# arduino.net
KiCad netlist of a schematic drawn in EAGLE
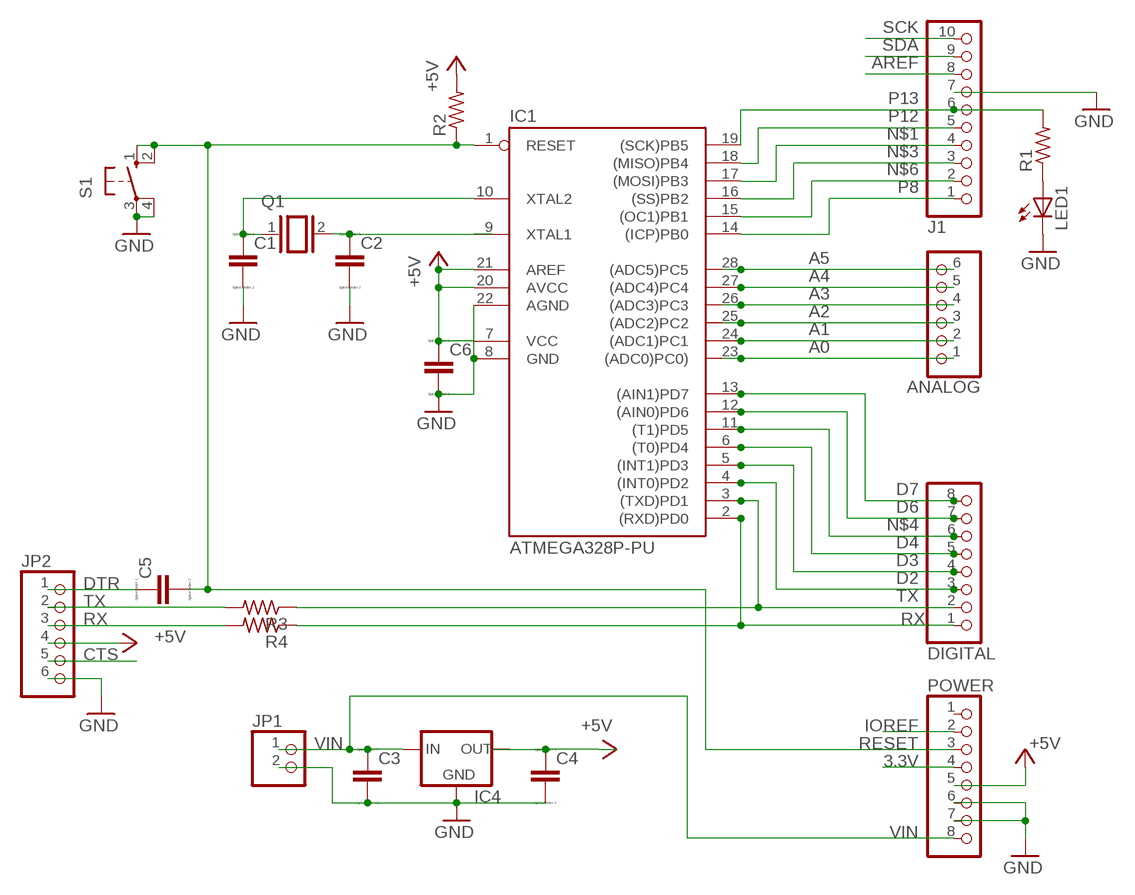
[diagram p0: schematic, sheet 1]

(export (version "E")
  (design (tool "Eeschema 10.0.6"))
  (components
    (comp (ref "ANALOG")
      (value "PINHD-1X6")
      (footprint "eagle-import:1X06")
      (libsource (lib "eagle-import") (part "PINHD-1X6"))
    )
    (comp (ref "C1")
      (value "C-EU050-025X075")
      (footprint "eagle-import:C050-025X075")
      (libsource (lib "eagle-import") (part "C-EU050-025X075"))
    )
    (comp (ref "C2")
      (value "C-EU050-025X075")
      (footprint "eagle-import:C050-025X075")
      (libsource (lib "eagle-import") (part "C-EU050-025X075"))
    )
    (comp (ref "C3")
      (value "C-EU050-025X075")
      (footprint "eagle-import:C050-025X075")
      (libsource (lib "eagle-import") (part "C-EU050-025X075"))
    )
    (comp (ref "C4")
      (value "C-EU050-025X075")
      (footprint "eagle-import:C050-025X075")
      (libsource (lib "eagle-import") (part "C-EU050-025X075"))
    )
    (comp (ref "C5")
      (value "C-EU050-025X075")
      (footprint "eagle-import:C050-025X075")
      (libsource (lib "eagle-import") (part "C-EU050-025X075"))
    )
    (comp (ref "C6")
      (value "C-EU050-025X075")
      (footprint "eagle-import:C050-025X075")
      (libsource (lib "eagle-import") (part "C-EU050-025X075"))
    )
    (comp (ref "DIGITAL")
      (value "PINHD-1X8TH")
      (footprint "eagle-import:1X08-TH")
      (libsource (lib "eagle-import") (part "PINHD-1X8TH"))
    )
    (comp (ref "IC1")
      (value "ATMEGA328P-PU")
      (footprint "eagle-import:DIL28-3")
      (libsource (lib "eagle-import") (part "ATMEGA328P-PU"))
    )
    (comp (ref "IC4")
      (value "78XXS")
      (footprint "eagle-import:78XXS")
      (libsource (lib "eagle-import") (part "78XXS"))
    )
    (comp (ref "J1")
      (value "PINHD-1X10TH")
      (footprint "eagle-import:1X10-TH")
      (libsource (lib "eagle-import") (part "PINHD-1X10TH"))
    )
    (comp (ref "JP1")
      (value "PINHD-1X2")
      (footprint "eagle-import:1X02")
      (libsource (lib "eagle-import") (part "PINHD-1X2"))
    )
    (comp (ref "JP2")
      (value "PINHD-1X6")
      (footprint "eagle-import:1X06")
      (libsource (lib "eagle-import") (part "PINHD-1X6"))
    )
    (comp (ref "LED1")
      (value "LED3MM")
      (footprint "eagle-import:LED3MM")
      (libsource (lib "eagle-import") (part "LED3MM"))
    )
    (comp (ref "POWER")
      (value "PINHD-1X8TH")
      (footprint "eagle-import:1X08-TH")
      (libsource (lib "eagle-import") (part "PINHD-1X8TH"))
    )
    (comp (ref "Q1")
      (value "XTAL/S")
      (footprint "eagle-import:QS")
      (libsource (lib "eagle-import") (part "XTAL/S"))
    )
    (comp (ref "R1")
      (value "R-US_0207/10")
      (footprint "eagle-import:0207_10")
      (libsource (lib "eagle-import") (part "R-US_0207/10"))
    )
    (comp (ref "R2")
      (value "R-US_0207/10")
      (footprint "eagle-import:0207_10")
      (libsource (lib "eagle-import") (part "R-US_0207/10"))
    )
    (comp (ref "R3")
      (value "R-US_0207/10")
      (footprint "eagle-import:0207_10")
      (libsource (lib "eagle-import") (part "R-US_0207/10"))
    )
    (comp (ref "R4")
      (value "R-US_0207/10")
      (footprint "eagle-import:0207_10")
      (libsource (lib "eagle-import") (part "R-US_0207/10"))
    )
    (comp (ref "S1")
      (value "10-XX")
      (footprint "eagle-import:B3F-10XX")
      (fields (field (name "MPN") "B3F-1000"))
      (libsource (lib "eagle-import") (part "10-XX"))
    )
  )
  (nets
    (net (code "1") (name "+5V") (class "Default")
      (node (ref "C4") (pin "1") (pinfunction "1_1") (pintype "passive"))
      (node (ref "C6") (pin "1") (pinfunction "1_1") (pintype "passive"))
      (node (ref "IC1") (pin "20") (pinfunction "AVCC_20") (pintype "power_in"))
      (node (ref "IC1") (pin "21") (pinfunction "AREF_21") (pintype "passive"))
      (node (ref "IC1") (pin "7") (pinfunction "VCC_7") (pintype "power_in"))
      (node (ref "IC4") (pin "OUT") (pinfunction "OUT_OUT") (pintype "passive"))
      (node (ref "JP2") (pin "4") (pinfunction "4_4") (pintype "passive"))
      (node (ref "POWER") (pin "5") (pinfunction "5_5") (pintype "passive"))
      (node (ref "R2") (pin "2") (pinfunction "2_2") (pintype "passive"))
    )
    (net (code "2") (name "/3.3V") (class "Default")
      (node (ref "POWER") (pin "4") (pinfunction "4_4") (pintype "passive"))
    )
    (net (code "3") (name "/A0") (class "Default")
      (node (ref "ANALOG") (pin "1") (pinfunction "1_1") (pintype "passive"))
      (node (ref "IC1") (pin "23") (pinfunction "(ADC0)PC0)_23") (pintype "bidirectional"))
    )
    (net (code "4") (name "/A1") (class "Default")
      (node (ref "ANALOG") (pin "2") (pinfunction "2_2") (pintype "passive"))
      (node (ref "IC1") (pin "24") (pinfunction "(ADC1)PC1_24") (pintype "bidirectional"))
    )
    (net (code "5") (name "/A2") (class "Default")
      (node (ref "ANALOG") (pin "3") (pinfunction "3_3") (pintype "passive"))
      (node (ref "IC1") (pin "25") (pinfunction "(ADC2)PC2_25") (pintype "bidirectional"))
    )
    (net (code "6") (name "/A3") (class "Default")
      (node (ref "ANALOG") (pin "4") (pinfunction "4_4") (pintype "passive"))
      (node (ref "IC1") (pin "26") (pinfunction "(ADC3)PC3_26") (pintype "bidirectional"))
    )
    (net (code "7") (name "/A4") (class "Default")
      (node (ref "ANALOG") (pin "5") (pinfunction "5_5") (pintype "passive"))
      (node (ref "IC1") (pin "27") (pinfunction "(ADC4)PC4_27") (pintype "bidirectional"))
    )
    (net (code "8") (name "/A5") (class "Default")
      (node (ref "ANALOG") (pin "6") (pinfunction "6_6") (pintype "passive"))
      (node (ref "IC1") (pin "28") (pinfunction "(ADC5)PC5_28") (pintype "bidirectional"))
    )
    (net (code "9") (name "/AREF") (class "Default")
      (node (ref "J1") (pin "8") (pinfunction "8_8") (pintype "passive"))
    )
    (net (code "10") (name "/CTS") (class "Default")
      (node (ref "JP2") (pin "5") (pinfunction "5_5") (pintype "passive"))
    )
    (net (code "11") (name "/D2") (class "Default")
      (node (ref "DIGITAL") (pin "3") (pinfunction "3_3") (pintype "passive"))
      (node (ref "IC1") (pin "4") (pinfunction "(INT0)PD2_4") (pintype "bidirectional"))
    )
    (net (code "12") (name "/D3") (class "Default")
      (node (ref "DIGITAL") (pin "4") (pinfunction "4_4") (pintype "passive"))
      (node (ref "IC1") (pin "5") (pinfunction "(INT1)PD3_5") (pintype "bidirectional"))
    )
    (net (code "13") (name "/D4") (class "Default")
      (node (ref "DIGITAL") (pin "5") (pinfunction "5_5") (pintype "passive"))
      (node (ref "IC1") (pin "6") (pinfunction "(T0)PD4_6") (pintype "bidirectional"))
    )
    (net (code "14") (name "/D6") (class "Default")
      (node (ref "DIGITAL") (pin "7") (pinfunction "7_7") (pintype "passive"))
      (node (ref "IC1") (pin "12") (pinfunction "(AIN0)PD6_12") (pintype "bidirectional"))
    )
    (net (code "15") (name "/D7") (class "Default")
      (node (ref "DIGITAL") (pin "8") (pinfunction "8_8") (pintype "passive"))
      (node (ref "IC1") (pin "13") (pinfunction "(AIN1)PD7_13") (pintype "bidirectional"))
    )
    (net (code "16") (name "/DTR") (class "Default")
      (node (ref "C5") (pin "1") (pinfunction "1_1") (pintype "passive"))
      (node (ref "JP2") (pin "1") (pinfunction "1_1") (pintype "passive"))
    )
    (net (code "17") (name "/IOREF") (class "Default")
      (node (ref "POWER") (pin "2") (pinfunction "2_2") (pintype "passive"))
    )
    (net (code "18") (name "/N$1") (class "Default")
      (node (ref "IC1") (pin "17") (pinfunction "(MOSI)PB3_17") (pintype "bidirectional"))
      (node (ref "J1") (pin "4") (pinfunction "4_4") (pintype "passive"))
    )
    (net (code "19") (name "/N$3") (class "Default")
      (node (ref "IC1") (pin "16") (pinfunction "(SS)PB2_16") (pintype "bidirectional"))
      (node (ref "J1") (pin "3") (pinfunction "3_3") (pintype "passive"))
    )
    (net (code "20") (name "/N$4") (class "Default")
      (node (ref "DIGITAL") (pin "6") (pinfunction "6_6") (pintype "passive"))
      (node (ref "IC1") (pin "11") (pinfunction "(T1)PD5_11") (pintype "bidirectional"))
    )
    (net (code "21") (name "/N$6") (class "Default")
      (node (ref "IC1") (pin "15") (pinfunction "(OC1)PB1_15") (pintype "bidirectional"))
      (node (ref "J1") (pin "2") (pinfunction "2_2") (pintype "passive"))
    )
    (net (code "22") (name "/P8") (class "Default")
      (node (ref "IC1") (pin "14") (pinfunction "(ICP)PB0_14") (pintype "bidirectional"))
      (node (ref "J1") (pin "1") (pinfunction "1_1") (pintype "passive"))
    )
    (net (code "23") (name "/P12") (class "Default")
      (node (ref "IC1") (pin "18") (pinfunction "(MISO)PB4_18") (pintype "bidirectional"))
      (node (ref "J1") (pin "5") (pinfunction "5_5") (pintype "passive"))
    )
    (net (code "24") (name "/P13") (class "Default")
      (node (ref "IC1") (pin "19") (pinfunction "(SCK)PB5_19") (pintype "bidirectional"))
      (node (ref "J1") (pin "6") (pinfunction "6_6") (pintype "passive"))
      (node (ref "R1") (pin "2") (pinfunction "2_2") (pintype "passive"))
    )
    (net (code "25") (name "/RESET") (class "Default")
      (node (ref "C5") (pin "2") (pinfunction "2_2") (pintype "passive"))
      (node (ref "IC1") (pin "1") (pinfunction "RESET_1") (pintype "input"))
      (node (ref "POWER") (pin "3") (pinfunction "3_3") (pintype "passive"))
      (node (ref "R2") (pin "1") (pinfunction "1_1") (pintype "passive"))
      (node (ref "S1") (pin "1") (pinfunction "S_1") (pintype "passive"))
      (node (ref "S1") (pin "2") (pinfunction "S1_2") (pintype "passive"))
    )
    (net (code "26") (name "/RX") (class "Default")
      (node (ref "DIGITAL") (pin "1") (pinfunction "1_1") (pintype "passive"))
      (node (ref "IC1") (pin "2") (pinfunction "(RXD)PD0_2") (pintype "bidirectional"))
      (node (ref "R4") (pin "1") (pinfunction "1_1") (pintype "passive"))
    )
    (net (code "27") (name "/SCK") (class "Default")
      (node (ref "J1") (pin "10") (pinfunction "10_10") (pintype "passive"))
    )
    (net (code "28") (name "/SDA") (class "Default")
      (node (ref "J1") (pin "9") (pinfunction "9_9") (pintype "passive"))
    )
    (net (code "29") (name "/TX") (class "Default")
      (node (ref "DIGITAL") (pin "2") (pinfunction "2_2") (pintype "passive"))
      (node (ref "IC1") (pin "3") (pinfunction "(TXD)PD1_3") (pintype "bidirectional"))
      (node (ref "R3") (pin "1") (pinfunction "1_1") (pintype "passive"))
    )
    (net (code "30") (name "/VIN") (class "Default")
      (node (ref "C3") (pin "1") (pinfunction "1_1") (pintype "passive"))
      (node (ref "IC4") (pin "IN") (pinfunction "IN_IN") (pintype "input"))
      (node (ref "JP1") (pin "1") (pinfunction "1_1") (pintype "passive"))
      (node (ref "POWER") (pin "8") (pinfunction "8_8") (pintype "passive"))
    )
    (net (code "31") (name "GND") (class "Default")
      (node (ref "C1") (pin "2") (pinfunction "2_2") (pintype "passive"))
      (node (ref "C2") (pin "2") (pinfunction "2_2") (pintype "passive"))
      (node (ref "C3") (pin "2") (pinfunction "2_2") (pintype "passive"))
      (node (ref "C4") (pin "2") (pinfunction "2_2") (pintype "passive"))
      (node (ref "C6") (pin "2") (pinfunction "2_2") (pintype "passive"))
      (node (ref "IC1") (pin "22") (pinfunction "AGND_22") (pintype "power_in"))
      (node (ref "IC1") (pin "8") (pinfunction "GND_8") (pintype "power_in"))
      (node (ref "IC4") (pin "GND") (pinfunction "GND_GND") (pintype "input"))
      (node (ref "J1") (pin "7") (pinfunction "7_7") (pintype "passive"))
      (node (ref "JP1") (pin "2") (pinfunction "2_2") (pintype "passive"))
      (node (ref "JP2") (pin "6") (pinfunction "6_6") (pintype "passive"))
      (node (ref "LED1") (pin "K") (pinfunction "C_K") (pintype "passive"))
      (node (ref "POWER") (pin "6") (pinfunction "6_6") (pintype "passive"))
      (node (ref "POWER") (pin "7") (pinfunction "7_7") (pintype "passive"))
      (node (ref "S1") (pin "3") (pinfunction "P_3") (pintype "passive"))
      (node (ref "S1") (pin "4") (pinfunction "P1_4") (pintype "passive"))
    )
    (net (code "32") (name "Net-(IC1-XTAL1)") (class "Default")
      (node (ref "C2") (pin "1") (pinfunction "1_1") (pintype "passive"))
      (node (ref "IC1") (pin "9") (pinfunction "XTAL1_9") (pintype "bidirectional"))
      (node (ref "Q1") (pin "2") (pinfunction "2_2") (pintype "passive"))
    )
    (net (code "33") (name "Net-(IC1-XTAL2)") (class "Default")
      (node (ref "C1") (pin "1") (pinfunction "1_1") (pintype "passive"))
      (node (ref "IC1") (pin "10") (pinfunction "XTAL2_10") (pintype "bidirectional"))
      (node (ref "Q1") (pin "1") (pinfunction "1_1") (pintype "passive"))
    )
    (net (code "34") (name "Net-(JP2-Pad2)") (class "Default")
      (node (ref "JP2") (pin "2") (pinfunction "2_2") (pintype "passive"))
      (node (ref "R3") (pin "2") (pinfunction "2_2") (pintype "passive"))
    )
    (net (code "35") (name "Net-(JP2-Pad3)") (class "Default")
      (node (ref "JP2") (pin "3") (pinfunction "3_3") (pintype "passive"))
      (node (ref "R4") (pin "2") (pinfunction "2_2") (pintype "passive"))
    )
    (net (code "36") (name "Net-(LED1-PadA)") (class "Default")
      (node (ref "LED1") (pin "A") (pinfunction "A_A") (pintype "passive"))
      (node (ref "R1") (pin "1") (pinfunction "1_1") (pintype "passive"))
    )
    (net (code "37") (name "unconnected-(POWER-Pad1)") (class "Default")
      (node (ref "POWER") (pin "1") (pinfunction "1_1") (pintype "passive"))
    )
  )
)
